# FireBeetle_ESP32_IoT.net
KiCad netlist of a schematic drawn in Altium Designer
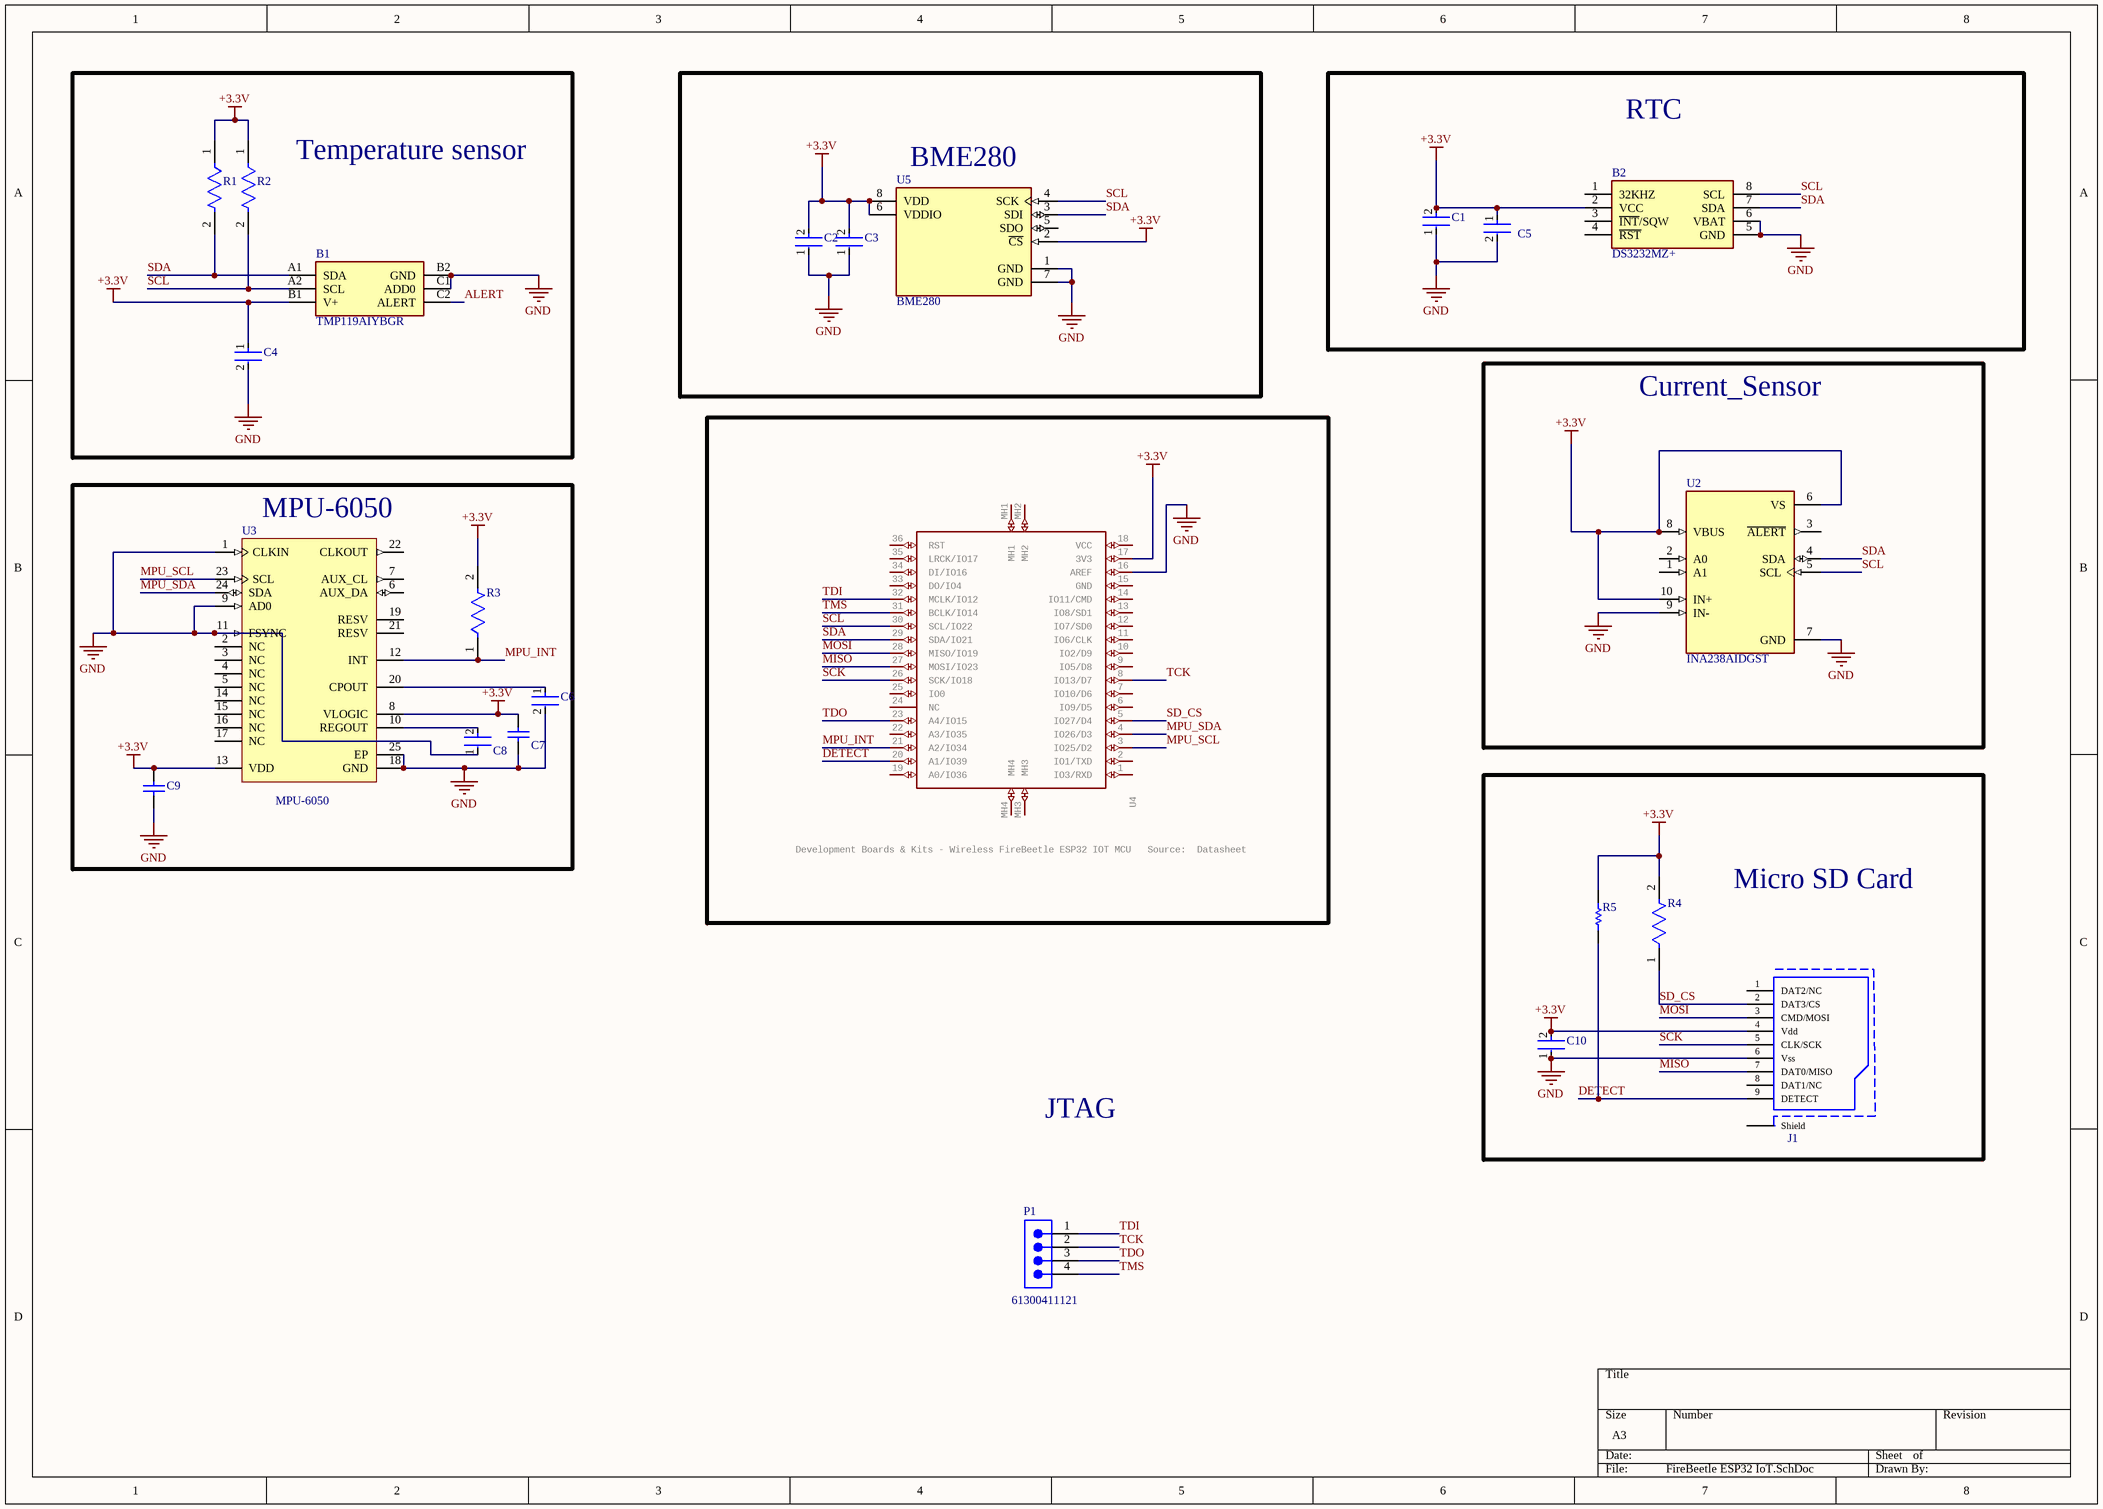
[diagram p0: FireBeetle ESP32 IoT.SchDoc]

(export (version "E")
  (design (tool "Eeschema 10.0.6"))
  (components
    (comp (ref "B1")
      (value "TMP119AIYBGR")
      (footprint "BGA6C40P2X3_95X149X52")
      (description "Board Mount Temperature Sensors TEMPERATURE SENSOR")
      (libsource (lib "TMP119AIYBGR") (part "TMP119AIYBGR"))
    )
    (comp (ref "B2")
      (value "DS3232MZ+")
      (footprint "SOIC127P600X175-8N")
      (description "Real Time Clock with SRAM I2C SOIC8 Maxim DS3232MZ+ Real Time Clock  Calendar, 236B RAM 8-Pin SOIC")
      (fields (field (name "MOUSER PART NUMBER") "700-DS3232MZ+"))
      (libsource (lib "DS3232MZ+") (part "DS3232MZ+"))
    )
    (comp (ref "C1")
      (value "GRM155R71C104KA88D")
      (footprint "FP-GRM15-MFG")
      (description "CAP CER 0.1UF 16V X7R 0402")
      (fields
        (field (name "TOLERANCE") "10%")
        (field (name "OCTOPART") "https://octopart.com/grm155r71c104ka88d-murata-196880")
      )
      (libsource (lib "Altium Content Vault") (part "236180d848d6139a670b325ea6854c9"))
    )
    (comp (ref "C2")
      (value "GRM155R71C104KA88D")
      (footprint "FP-GRM15-MFG")
      (description "CAP CER 0.1UF 16V X7R 0402")
      (fields
        (field (name "TOLERANCE") "10%")
        (field (name "OCTOPART") "https://octopart.com/grm155r71c104ka88d-murata-196880")
      )
      (libsource (lib "Altium Content Vault") (part "236180d848d6139a670b325ea6854c9"))
    )
    (comp (ref "C3")
      (value "GRM155R71C104KA88D")
      (footprint "FP-GRM15-MFG")
      (description "CAP CER 0.1UF 16V X7R 0402")
      (fields
        (field (name "TOLERANCE") "10%")
        (field (name "OCTOPART") "https://octopart.com/grm155r71c104ka88d-murata-196880")
      )
      (libsource (lib "Altium Content Vault") (part "236180d848d6139a670b325ea6854c9"))
    )
    (comp (ref "C4")
      (value "CC0201KRX5R5BB104")
      (footprint "FP-CC0201-BA-MFG")
      (description "CAP CER 0.1UF 6.3V X5R 0201")
      (fields (field (name "MANUFACTURER") "Yageo") (field (name "TOLERANCE") "0.1"))
      (libsource (lib "Altium Content Vault") (part "11868f565c42a9108669ba33697ecf6"))
    )
    (comp (ref "C5")
      (value "GRM155R61A105KE15D")
      (footprint "FP-GRM15-0_1-MFG")
      (description "CAP CER 1UF 10V X5R 0402")
      (fields
        (field (name "OCTOPART") "https://octopart.com/grm155r61a105ke15d-murata-197442")
        (field (name "MANUFACTURER") "Murata")
      )
      (libsource (lib "Altium Content Vault") (part "02cd4be3c70576c341d710602a673aa"))
    )
    (comp (ref "C6")
      (value "GRM155R71H222KA01D")
      (footprint "FP-GRM155-0_05-IPC_B")
      (description "Chip Multilayer Ceramic Capacitors for General Purpose, 0402, 2200pF, X7R, 15%, 10%, 50V")
      (fields (field (name "VOLTAGE") "50V") (field (name "TOLERANCE") "10%"))
      (libsource (lib "Altium Content Vault") (part "02cd4be3c70576c341d710602a673aa"))
    )
    (comp (ref "C7")
      (value "GRM155R71E103KA01D")
      (footprint "CAPC1005X55X25ML05T10")
      (fields (field (name "MANUFACTURER") "Murata"))
      (libsource (lib "Altium Content Vault") (part "CAP"))
    )
    (comp (ref "C8")
      (value "GRM155R71C104KA88D")
      (footprint "FP-GRM15-MFG")
      (description "CAP CER 0.1UF 16V X7R 0402")
      (fields
        (field (name "TOLERANCE") "10%")
        (field (name "OCTOPART") "https://octopart.com/grm155r71c104ka88d-murata-196880")
      )
      (libsource (lib "Altium Content Vault") (part "236180d848d6139a670b325ea6854c9"))
    )
    (comp (ref "C9")
      (value "GRM155R61A104KA01D")
      (footprint "CAPC1005X55X25ML5T10")
      (description "Chip Capacitor, 100 nF, +/- 10%, 10 V, -55 to 85 degC, 0402 (1005 Metric), RoHS, Tape and Reel")
      (fields (field (name "TOLERANCE") "10%"))
      (libsource (lib "Altium Content Vault") (part "CAP-NP-2"))
    )
    (comp (ref "C10")
      (value "GRM155R71C104KA88D")
      (footprint "FP-GRM15-MFG")
      (description "CAP CER 0.1UF 16V X7R 0402")
      (fields
        (field (name "TOLERANCE") "10%")
        (field (name "OCTOPART") "https://octopart.com/grm155r71c104ka88d-murata-196880")
      )
      (libsource (lib "Altium Content Vault") (part "236180d848d6139a670b325ea6854c9"))
    )
    (comp (ref "J1")
      (value "Micro SD")
      (footprint "TFP-09-2-12B")
      (fields (field (name "PARTNUMBER") "TFP-09-2-12B"))
      (libsource (lib "Conn Card") (part "Micro SD TFP-09-2-12B"))
    )
    (comp (ref "P1")
      (value "61300411121")
      (footprint "61300411121")
      (libsource (lib "Altium Content Vault") (part "Header_Male_1R_04P"))
    )
    (comp (ref "R1")
      (value "ERJ-1GNF4701C")
      (footprint "FP-ERJ0201-MFG")
      (description "RES SMD 4.7K OHM 1% 1/20W 0201")
      (fields
        (field (name "MANUFACTURER") "Panasonic Electronic Components")
        (field (name "OCTOPART") "https://octopart.com/erj-1gnf4701c-panasonic-55560010")
      )
      (libsource (lib "Altium Content Vault") (part "1029c3af85768c4190bb7ad29bc67b5"))
    )
    (comp (ref "R2")
      (value "ERJ-1GNF4701C")
      (footprint "FP-ERJ0201-MFG")
      (description "RES SMD 4.7K OHM 1% 1/20W 0201")
      (fields
        (field (name "MANUFACTURER") "Panasonic Electronic Components")
        (field (name "OCTOPART") "https://octopart.com/erj-1gnf4701c-panasonic-55560010")
      )
      (libsource (lib "Altium Content Vault") (part "1029c3af85768c4190bb7ad29bc67b5"))
    )
    (comp (ref "R3")
      (value "ERJ-2RKF1003X")
      (footprint "FP-ERJ2RK-IPC_C")
      (description "RES SMD 100K OHM 1% 1/10W 0402")
      (fields (field (name "TOLERANCE") "1%"))
      (libsource (lib "Altium Content Vault") (part "1029c3af85768c4190bb7ad29bc67b5"))
    )
    (comp (ref "R4")
      (value "ERJ-2RKF1003X")
      (footprint "FP-ERJ2RK-IPC_C")
      (description "RES SMD 100K OHM 1% 1/10W 0402")
      (fields (field (name "TOLERANCE") "1%"))
      (libsource (lib "Altium Content Vault") (part "1029c3af85768c4190bb7ad29bc67b5"))
    )
    (comp (ref "R5")
      (value "ERJ-2RKF1004X")
      (footprint "RESC1005X40X25LL05T05")
      (description "Chip Resistor, 1 MOhm, +/- 1%, 100 mW, -55 to 155 degC, 0402 (1005 Metric), RoHS, Tape and Reel")
      (fields (field (name "TOLERANCE") "1%") (field (name "MANUFACTURER") "Basic Passives"))
      (libsource (lib "Altium Content Vault") (part "RES-2"))
    )
    (comp (ref "U2")
      (value "INA238AIDGST")
      (footprint "SOP50P490X110-10N")
      (libsource (lib "INA238AIDGST") (part "INA238AIDGST"))
    )
    (comp (ref "U3")
      (value "MPU-6050")
      (footprint "IS-QFN-24_V")
      (fields (field (name "MANUFACTURER") "InvenSense"))
      (libsource (lib "Altium Content Vault") (part "IS-MPU-6050-QFN-24"))
    )
    (comp (ref "U4")
      (value "Development Boards & Kits - Wireless FireBeetle ESP32 IOT MCU   Source:  Datasheet")
      (footprint "FIREBEETLE_ESP32")
      (fields
        (field (name "MANUFACTURER_PART_NUMBER") "DFR0478")
        (field (name "MOUSER_PART_NUMBER") "426-DFR0478")
      )
      (libsource (lib "DFR0478") (part "DFR0478"))
    )
    (comp (ref "U5")
      (value "BME280")
      (footprint "FP-BME280-MFG")
      (description "SENSOR PRESSURE HUMIDITY TEMP")
      (libsource (lib "Altium Content Vault") (part "d58e2f6669bc67e6a2bc6a28610ca79"))
    )
  )
  (nets
    (net (code "1") (name "+3.3V") (class "Default")
      (node (ref "B1") (pin "B1") (pinfunction "V+_B1") (pintype "passive"))
      (node (ref "B2") (pin "2") (pinfunction "VCC_2") (pintype "passive"))
      (node (ref "C1") (pin "2") (pinfunction "2_2") (pintype "passive"))
      (node (ref "C10") (pin "2") (pinfunction "2_2") (pintype "passive"))
      (node (ref "C2") (pin "2") (pinfunction "2_2") (pintype "passive"))
      (node (ref "C3") (pin "2") (pinfunction "2_2") (pintype "passive"))
      (node (ref "C4") (pin "1") (pinfunction "1_1") (pintype "passive"))
      (node (ref "C5") (pin "1") (pinfunction "1_1") (pintype "passive"))
      (node (ref "C7") (pin "2") (pinfunction "2_2") (pintype "passive"))
      (node (ref "C9") (pin "2") (pinfunction "2_2") (pintype "passive"))
      (node (ref "J1") (pin "4") (pinfunction "Vdd_4") (pintype "passive"))
      (node (ref "R1") (pin "1") (pinfunction "1_1") (pintype "passive"))
      (node (ref "R2") (pin "1") (pinfunction "1_1") (pintype "passive"))
      (node (ref "R3") (pin "2") (pinfunction "2_2") (pintype "passive"))
      (node (ref "R4") (pin "2") (pinfunction "2_2") (pintype "passive"))
      (node (ref "R5") (pin "2") (pinfunction "2_2") (pintype "passive"))
      (node (ref "U2") (pin "10") (pinfunction "IN+_10") (pintype "input"))
      (node (ref "U2") (pin "6") (pinfunction "VS_6") (pintype "power_in"))
      (node (ref "U2") (pin "8") (pinfunction "VBUS_8") (pintype "input"))
      (node (ref "U3") (pin "13") (pinfunction "VDD_13") (pintype "power_in"))
      (node (ref "U3") (pin "8") (pinfunction "VLOGIC_8") (pintype "power_in"))
      (node (ref "U4") (pin "17") (pinfunction "3V3_17") (pintype "bidirectional"))
      (node (ref "U5") (pin "2") (pinfunction "~{CS}_2") (pintype "input"))
      (node (ref "U5") (pin "6") (pinfunction "VDDIO_6") (pintype "power_in"))
      (node (ref "U5") (pin "8") (pinfunction "VDD_8") (pintype "power_in"))
    )
    (net (code "2") (name "/ALERT") (class "Default")
      (node (ref "B1") (pin "C2") (pinfunction "ALERT_C2") (pintype "passive"))
    )
    (net (code "3") (name "/DETECT") (class "Default")
      (node (ref "J1") (pin "9") (pinfunction "DETECT_9") (pintype "passive"))
      (node (ref "R5") (pin "1") (pinfunction "1_1") (pintype "passive"))
      (node (ref "U4") (pin "20") (pinfunction "A1/IO39_20") (pintype "bidirectional"))
    )
    (net (code "4") (name "/MISO") (class "Default")
      (node (ref "J1") (pin "7") (pinfunction "DAT0/MISO_7") (pintype "passive"))
      (node (ref "U4") (pin "27") (pinfunction "MOSI/IO23_27") (pintype "bidirectional"))
    )
    (net (code "5") (name "/MOSI") (class "Default")
      (node (ref "J1") (pin "3") (pinfunction "CMD/MOSI_3") (pintype "passive"))
      (node (ref "U4") (pin "28") (pinfunction "MISO/IO19_28") (pintype "bidirectional"))
    )
    (net (code "6") (name "/MPU_INT") (class "Default")
      (node (ref "R3") (pin "1") (pinfunction "1_1") (pintype "passive"))
      (node (ref "U3") (pin "12") (pinfunction "INT_12") (pintype "open_collector"))
      (node (ref "U4") (pin "21") (pinfunction "A2/IO34_21") (pintype "bidirectional"))
    )
    (net (code "7") (name "/MPU_SCL") (class "Default")
      (node (ref "U3") (pin "23") (pinfunction "SCL_23") (pintype "input"))
      (node (ref "U4") (pin "3") (pinfunction "IO25/D2_3") (pintype "bidirectional"))
    )
    (net (code "8") (name "/MPU_SDA") (class "Default")
      (node (ref "U3") (pin "24") (pinfunction "SDA_24") (pintype "bidirectional"))
      (node (ref "U4") (pin "4") (pinfunction "IO26/D3_4") (pintype "bidirectional"))
    )
    (net (code "9") (name "/SCK") (class "Default")
      (node (ref "J1") (pin "5") (pinfunction "CLK/SCK_5") (pintype "passive"))
      (node (ref "U4") (pin "26") (pinfunction "SCK/IO18_26") (pintype "bidirectional"))
    )
    (net (code "10") (name "/SCL") (class "Default")
      (node (ref "B1") (pin "A2") (pinfunction "SCL_A2") (pintype "passive"))
      (node (ref "B2") (pin "8") (pinfunction "SCL_8") (pintype "passive"))
      (node (ref "R2") (pin "2") (pinfunction "2_2") (pintype "passive"))
      (node (ref "U2") (pin "5") (pinfunction "SCL_5") (pintype "input"))
      (node (ref "U4") (pin "30") (pinfunction "SCL/IO22_30") (pintype "bidirectional"))
      (node (ref "U5") (pin "4") (pinfunction "SCK_4") (pintype "input"))
    )
    (net (code "11") (name "/SDA") (class "Default")
      (node (ref "B1") (pin "A1") (pinfunction "SDA_A1") (pintype "passive"))
      (node (ref "B2") (pin "7") (pinfunction "SDA_7") (pintype "passive"))
      (node (ref "R1") (pin "2") (pinfunction "2_2") (pintype "passive"))
      (node (ref "U2") (pin "4") (pinfunction "SDA_4") (pintype "bidirectional"))
      (node (ref "U4") (pin "29") (pinfunction "SDA/IO21_29") (pintype "bidirectional"))
      (node (ref "U5") (pin "3") (pinfunction "SDI_3") (pintype "bidirectional"))
    )
    (net (code "12") (name "/SD_CS") (class "Default")
      (node (ref "J1") (pin "2") (pinfunction "DAT3/CS_2") (pintype "passive"))
      (node (ref "R4") (pin "1") (pinfunction "1_1") (pintype "passive"))
      (node (ref "U4") (pin "5") (pinfunction "IO27/D4_5") (pintype "bidirectional"))
    )
    (net (code "13") (name "/TCK") (class "Default")
      (node (ref "P1") (pin "2") (pinfunction "2_2") (pintype "passive"))
      (node (ref "U4") (pin "8") (pinfunction "IO13/D7_8") (pintype "bidirectional"))
    )
    (net (code "14") (name "/TDI") (class "Default")
      (node (ref "P1") (pin "1") (pinfunction "1_1") (pintype "passive"))
      (node (ref "U4") (pin "32") (pinfunction "MCLK/IO12_32") (pintype "bidirectional"))
    )
    (net (code "15") (name "/TDO") (class "Default")
      (node (ref "P1") (pin "3") (pinfunction "3_3") (pintype "passive"))
      (node (ref "U4") (pin "23") (pinfunction "A4/IO15_23") (pintype "bidirectional"))
    )
    (net (code "16") (name "/TMS") (class "Default")
      (node (ref "P1") (pin "4") (pinfunction "4_4") (pintype "passive"))
      (node (ref "U4") (pin "31") (pinfunction "BCLK/IO14_31") (pintype "bidirectional"))
    )
    (net (code "17") (name "GND") (class "Default")
      (node (ref "B1") (pin "B2") (pinfunction "GND_B2") (pintype "passive"))
      (node (ref "B1") (pin "C1") (pinfunction "ADD0_C1") (pintype "passive"))
      (node (ref "B2") (pin "5") (pinfunction "GND_5") (pintype "passive"))
      (node (ref "B2") (pin "6") (pinfunction "VBAT_6") (pintype "passive"))
      (node (ref "C1") (pin "1") (pinfunction "1_1") (pintype "passive"))
      (node (ref "C10") (pin "1") (pinfunction "1_1") (pintype "passive"))
      (node (ref "C2") (pin "1") (pinfunction "1_1") (pintype "passive"))
      (node (ref "C3") (pin "1") (pinfunction "1_1") (pintype "passive"))
      (node (ref "C4") (pin "2") (pinfunction "2_2") (pintype "passive"))
      (node (ref "C5") (pin "2") (pinfunction "2_2") (pintype "passive"))
      (node (ref "C6") (pin "2") (pinfunction "2_2") (pintype "passive"))
      (node (ref "C7") (pin "1") (pinfunction "1_1") (pintype "passive"))
      (node (ref "C8") (pin "1") (pinfunction "1_1") (pintype "passive"))
      (node (ref "C9") (pin "1") (pinfunction "1_1") (pintype "passive"))
      (node (ref "J1") (pin "6") (pinfunction "Vss_6") (pintype "passive"))
      (node (ref "U2") (pin "7") (pinfunction "GND_7") (pintype "power_in"))
      (node (ref "U2") (pin "9") (pinfunction "IN-_9") (pintype "input"))
      (node (ref "U3") (pin "1") (pinfunction "CLKIN_1") (pintype "input"))
      (node (ref "U3") (pin "11") (pinfunction "FSYNC_11") (pintype "input"))
      (node (ref "U3") (pin "18") (pinfunction "GND_18") (pintype "power_in"))
      (node (ref "U3") (pin "25") (pinfunction "EP_25") (pintype "power_in"))
      (node (ref "U3") (pin "9") (pinfunction "AD0_9") (pintype "input"))
      (node (ref "U4") (pin "16") (pinfunction "AREF_16") (pintype "bidirectional"))
      (node (ref "U5") (pin "1") (pinfunction "GND_1") (pintype "power_in"))
      (node (ref "U5") (pin "7") (pinfunction "GND_7") (pintype "power_in"))
    )
    (net (code "18") (name "Net-(U3-CPOUT)") (class "Default")
      (node (ref "C6") (pin "1") (pinfunction "1_1") (pintype "passive"))
      (node (ref "U3") (pin "20") (pinfunction "CPOUT_20") (pintype "passive"))
    )
    (net (code "19") (name "Net-(U3-REGOUT)") (class "Default")
      (node (ref "C8") (pin "2") (pinfunction "2_2") (pintype "passive"))
      (node (ref "U3") (pin "10") (pinfunction "REGOUT_10") (pintype "passive"))
    )
    (net (code "20") (name "unconnected-(B2-32KHZ-Pad1)") (class "Default")
      (node (ref "B2") (pin "1") (pinfunction "32KHZ_1") (pintype "passive"))
    )
    (net (code "21") (name "unconnected-(B2-~{INT}{slash}SQW-Pad3)") (class "Default")
      (node (ref "B2") (pin "3") (pinfunction "~{INT}/SQW_3") (pintype "passive"))
    )
    (net (code "22") (name "unconnected-(B2-~{RST}-Pad4)") (class "Default")
      (node (ref "B2") (pin "4") (pinfunction "~{RST}_4") (pintype "passive"))
    )
    (net (code "23") (name "unconnected-(J1-DAT1{slash}NC-Pad8)") (class "Default")
      (node (ref "J1") (pin "8") (pinfunction "DAT1/NC_8") (pintype "passive"))
    )
    (net (code "24") (name "unconnected-(J1-DAT2{slash}NC-Pad1)") (class "Default")
      (node (ref "J1") (pin "1") (pinfunction "DAT2/NC_1") (pintype "passive"))
    )
    (net (code "25") (name "unconnected-(J1-Shield-Pad10)") (class "Default")
      (node (ref "J1") (pin "10") (pinfunction "Shield_10") (pintype "passive"))
    )
    (net (code "26") (name "unconnected-(U2-A0-Pad2)") (class "Default")
      (node (ref "U2") (pin "2") (pinfunction "A0_2") (pintype "input"))
    )
    (net (code "27") (name "unconnected-(U2-A1-Pad1)") (class "Default")
      (node (ref "U2") (pin "1") (pinfunction "A1_1") (pintype "input"))
    )
    (net (code "28") (name "unconnected-(U2-~{ALERT}-Pad3)") (class "Default")
      (node (ref "U2") (pin "3") (pinfunction "~{ALERT}_3") (pintype "output"))
    )
    (net (code "29") (name "unconnected-(U3-AUX_CL-Pad7)") (class "Default")
      (node (ref "U3") (pin "7") (pinfunction "AUX_CL_7") (pintype "output"))
    )
    (net (code "30") (name "unconnected-(U3-AUX_DA-Pad6)") (class "Default")
      (node (ref "U3") (pin "6") (pinfunction "AUX_DA_6") (pintype "bidirectional"))
    )
    (net (code "31") (name "unconnected-(U3-CLKOUT-Pad22)") (class "Default")
      (node (ref "U3") (pin "22") (pinfunction "CLKOUT_22") (pintype "output"))
    )
    (net (code "32") (name "unconnected-(U3-NC-Pad2)") (class "Default")
      (node (ref "U3") (pin "2") (pinfunction "NC_2") (pintype "passive"))
    )
    (net (code "33") (name "unconnected-(U3-NC-Pad3)") (class "Default")
      (node (ref "U3") (pin "3") (pinfunction "NC_3") (pintype "passive"))
    )
    (net (code "34") (name "unconnected-(U3-NC-Pad4)") (class "Default")
      (node (ref "U3") (pin "4") (pinfunction "NC_4") (pintype "passive"))
    )
    (net (code "35") (name "unconnected-(U3-NC-Pad5)") (class "Default")
      (node (ref "U3") (pin "5") (pinfunction "NC_5") (pintype "passive"))
    )
    (net (code "36") (name "unconnected-(U3-NC-Pad14)") (class "Default")
      (node (ref "U3") (pin "14") (pinfunction "NC_14") (pintype "passive"))
    )
    (net (code "37") (name "unconnected-(U3-NC-Pad15)") (class "Default")
      (node (ref "U3") (pin "15") (pinfunction "NC_15") (pintype "passive"))
    )
    (net (code "38") (name "unconnected-(U3-NC-Pad16)") (class "Default")
      (node (ref "U3") (pin "16") (pinfunction "NC_16") (pintype "passive"))
    )
    (net (code "39") (name "unconnected-(U3-NC-Pad17)") (class "Default")
      (node (ref "U3") (pin "17") (pinfunction "NC_17") (pintype "passive"))
    )
    (net (code "40") (name "unconnected-(U3-RESV-Pad19)") (class "Default")
      (node (ref "U3") (pin "19") (pinfunction "RESV_19") (pintype "passive"))
    )
    (net (code "41") (name "unconnected-(U3-RESV-Pad21)") (class "Default")
      (node (ref "U3") (pin "21") (pinfunction "RESV_21") (pintype "passive"))
    )
    (net (code "42") (name "unconnected-(U4-A0{slash}IO36-Pad19)") (class "Default")
      (node (ref "U4") (pin "19") (pinfunction "A0/IO36_19") (pintype "bidirectional"))
    )
    (net (code "43") (name "unconnected-(U4-A3{slash}IO35-Pad22)") (class "Default")
      (node (ref "U4") (pin "22") (pinfunction "A3/IO35_22") (pintype "bidirectional"))
    )
    (net (code "44") (name "unconnected-(U4-DI{slash}IO16-Pad34)") (class "Default")
      (node (ref "U4") (pin "34") (pinfunction "DI/IO16_34") (pintype "bidirectional"))
    )
    (net (code "45") (name "unconnected-(U4-DO{slash}IO4-Pad33)") (class "Default")
      (node (ref "U4") (pin "33") (pinfunction "DO/IO4_33") (pintype "bidirectional"))
    )
    (net (code "46") (name "unconnected-(U4-GND-Pad15)") (class "Default")
      (node (ref "U4") (pin "15") (pinfunction "GND_15") (pintype "bidirectional"))
    )
    (net (code "47") (name "unconnected-(U4-IO0-Pad25)") (class "Default")
      (node (ref "U4") (pin "25") (pinfunction "IO0_25") (pintype "bidirectional"))
    )
    (net (code "48") (name "unconnected-(U4-IO1{slash}TXD-Pad2)") (class "Default")
      (node (ref "U4") (pin "2") (pinfunction "IO1/TXD_2") (pintype "bidirectional"))
    )
    (net (code "49") (name "unconnected-(U4-IO2{slash}D9-Pad10)") (class "Default")
      (node (ref "U4") (pin "10") (pinfunction "IO2/D9_10") (pintype "bidirectional"))
    )
    (net (code "50") (name "unconnected-(U4-IO3{slash}RXD-Pad1)") (class "Default")
      (node (ref "U4") (pin "1") (pinfunction "IO3/RXD_1") (pintype "bidirectional"))
    )
    (net (code "51") (name "unconnected-(U4-IO5{slash}D8-Pad9)") (class "Default")
      (node (ref "U4") (pin "9") (pinfunction "IO5/D8_9") (pintype "bidirectional"))
    )
    (net (code "52") (name "unconnected-(U4-IO6{slash}CLK-Pad11)") (class "Default")
      (node (ref "U4") (pin "11") (pinfunction "IO6/CLK_11") (pintype "bidirectional"))
    )
    (net (code "53") (name "unconnected-(U4-IO7{slash}SD0-Pad12)") (class "Default")
      (node (ref "U4") (pin "12") (pinfunction "IO7/SD0_12") (pintype "bidirectional"))
    )
    (net (code "54") (name "unconnected-(U4-IO8{slash}SD1-Pad13)") (class "Default")
      (node (ref "U4") (pin "13") (pinfunction "IO8/SD1_13") (pintype "bidirectional"))
    )
    (net (code "55") (name "unconnected-(U4-IO9{slash}D5-Pad6)") (class "Default")
      (node (ref "U4") (pin "6") (pinfunction "IO9/D5_6") (pintype "bidirectional"))
    )
    (net (code "56") (name "unconnected-(U4-IO10{slash}D6-Pad7)") (class "Default")
      (node (ref "U4") (pin "7") (pinfunction "IO10/D6_7") (pintype "bidirectional"))
    )
    (net (code "57") (name "unconnected-(U4-IO11{slash}CMD-Pad14)") (class "Default")
      (node (ref "U4") (pin "14") (pinfunction "IO11/CMD_14") (pintype "bidirectional"))
    )
    (net (code "58") (name "unconnected-(U4-LRCK{slash}IO17-Pad35)") (class "Default")
      (node (ref "U4") (pin "35") (pinfunction "LRCK/IO17_35") (pintype "bidirectional"))
    )
    (net (code "59") (name "unconnected-(U4-NC-Pad24)") (class "Default")
      (node (ref "U4") (pin "24") (pinfunction "NC_24") (pintype "passive"))
    )
    (net (code "60") (name "unconnected-(U4-PadMH1)") (class "Default")
      (node (ref "U4") (pin "MH1") (pinfunction "MH1_MH1") (pintype "bidirectional"))
    )
    (net (code "61") (name "unconnected-(U4-PadMH2)") (class "Default")
      (node (ref "U4") (pin "MH2") (pinfunction "MH2_MH2") (pintype "bidirectional"))
    )
    (net (code "62") (name "unconnected-(U4-PadMH3)") (class "Default")
      (node (ref "U4") (pin "MH3") (pinfunction "MH3_MH3") (pintype "bidirectional"))
    )
    (net (code "63") (name "unconnected-(U4-PadMH4)") (class "Default")
      (node (ref "U4") (pin "MH4") (pinfunction "MH4_MH4") (pintype "bidirectional"))
    )
    (net (code "64") (name "unconnected-(U4-RST-Pad36)") (class "Default")
      (node (ref "U4") (pin "36") (pinfunction "RST_36") (pintype "bidirectional"))
    )
    (net (code "65") (name "unconnected-(U4-VCC-Pad18)") (class "Default")
      (node (ref "U4") (pin "18") (pinfunction "VCC_18") (pintype "bidirectional"))
    )
    (net (code "66") (name "unconnected-(U5-SDO-Pad5)") (class "Default")
      (node (ref "U5") (pin "5") (pinfunction "SDO_5") (pintype "bidirectional"))
    )
  )
)
